# Relay_Shield_v3_0.net
KiCad netlist of a schematic drawn in EAGLE
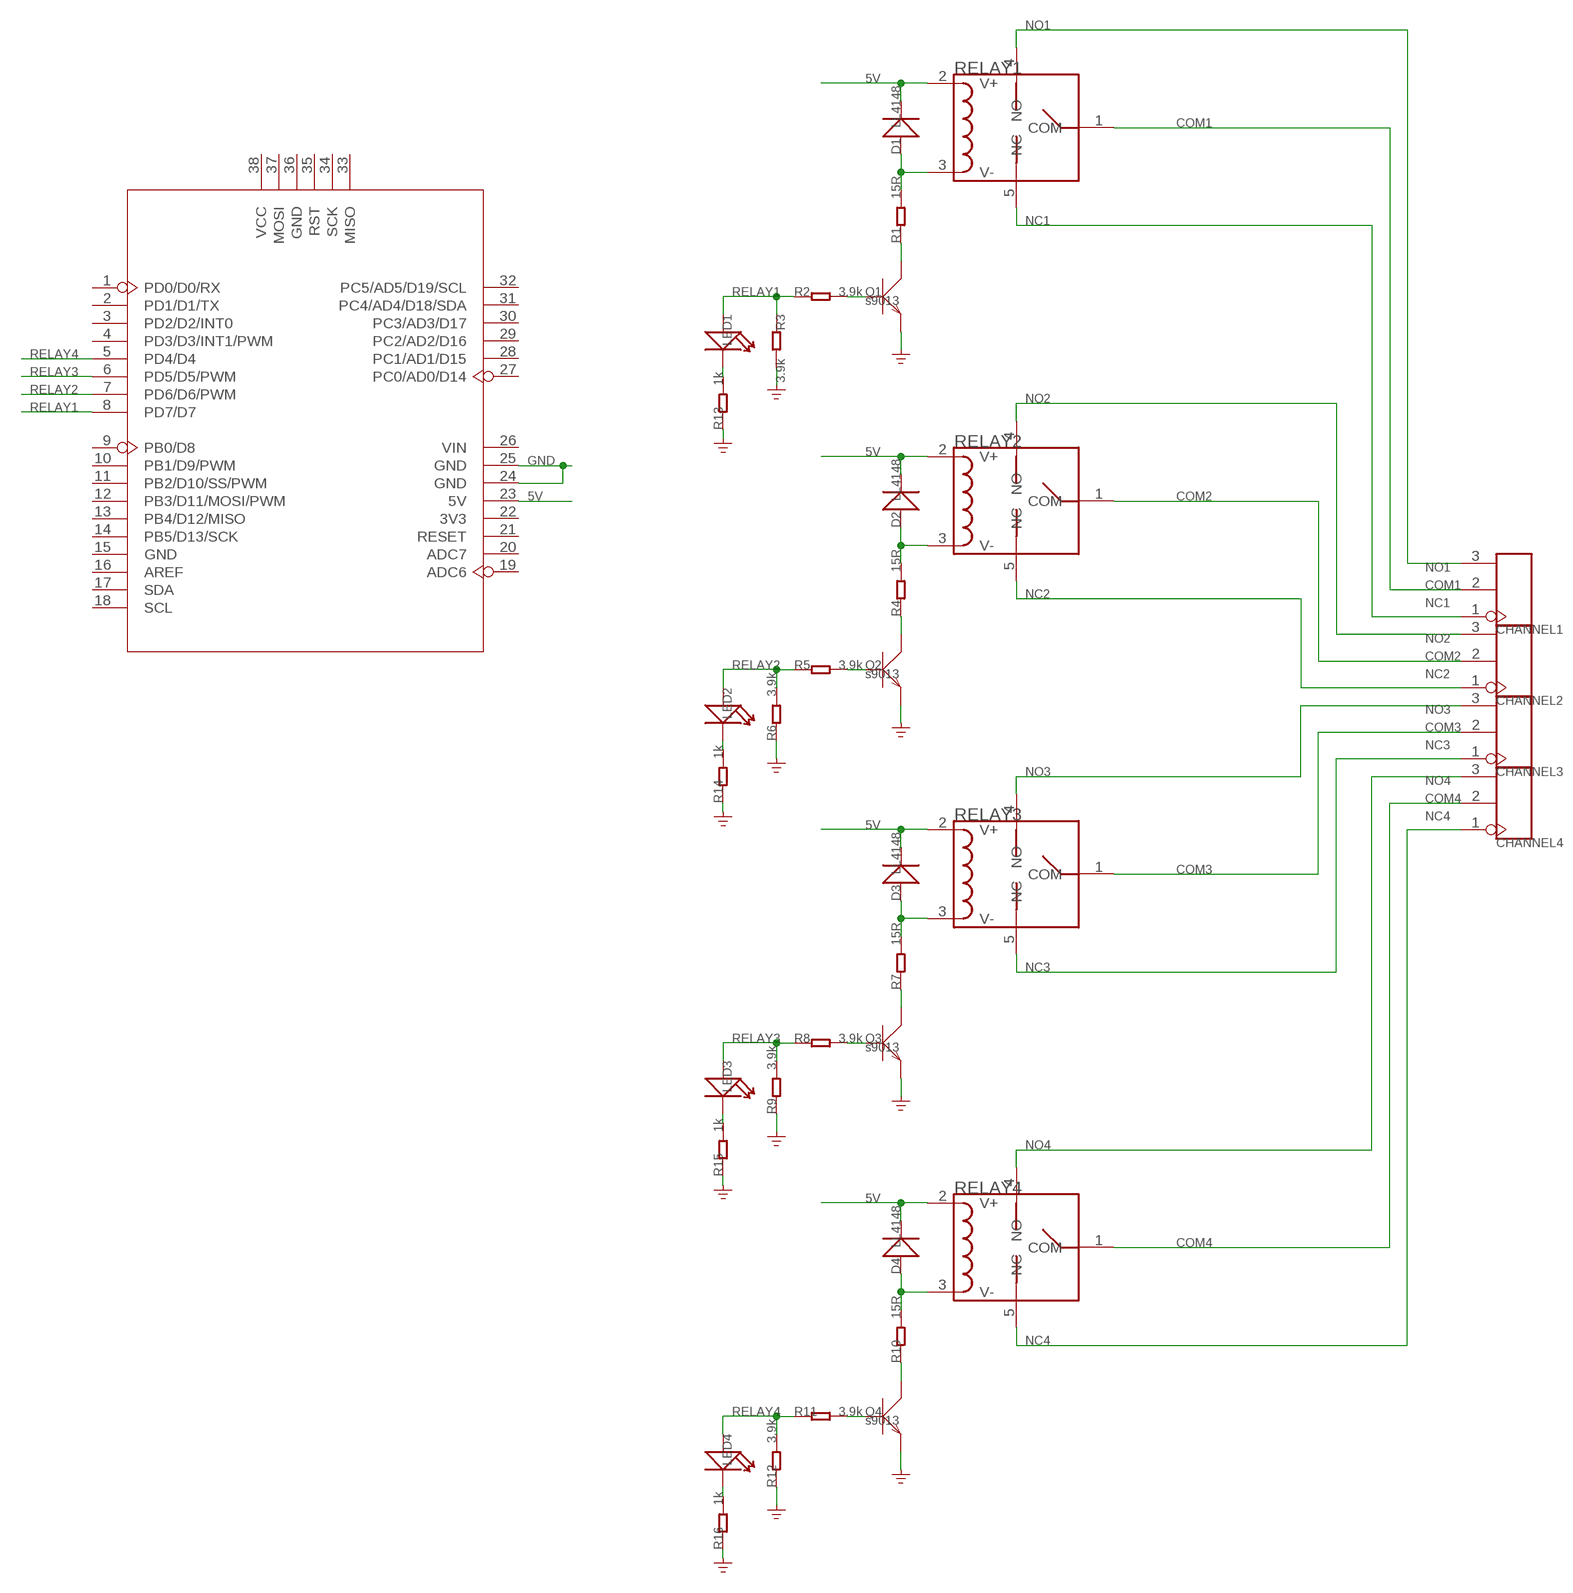
[diagram p0: schematic, sheet 1]
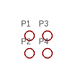
[diagram p1: schematic, sheet 2]

(export (version "E")
  (design (tool "Eeschema 10.0.6"))
  (components
    (comp (ref "P1")
      (value "PAD-MARK")
      (footprint "eagle-import:ROUND-MARK-1.0")
      (fields (field (name "PARTNO") "DNP"))
      (libsource (lib "eagle-import") (part "PAD-MARK"))
    )
    (comp (ref "P2")
      (value "PAD-MARK")
      (footprint "eagle-import:ROUND-MARK-1.0")
      (fields (field (name "PARTNO") "DNP"))
      (libsource (lib "eagle-import") (part "PAD-MARK"))
    )
    (comp (ref "P3")
      (value "PAD-MARK")
      (footprint "eagle-import:ROUND-MARK-1.0")
      (fields (field (name "PARTNO") "DNP"))
      (libsource (lib "eagle-import") (part "PAD-MARK"))
    )
    (comp (ref "P4")
      (value "PAD-MARK")
      (footprint "eagle-import:ROUND-MARK-1.0")
      (fields (field (name "PARTNO") "DNP"))
      (libsource (lib "eagle-import") (part "PAD-MARK"))
    )
    (comp (ref "CHANNEL1")
      (value "SCREW-TERMINAL-3P'3.5'")
      (footprint "eagle-import:3P-3.5")
      (libsource (lib "eagle-import") (part "SCREW-TERMINAL-3P'3.5'"))
    )
    (comp (ref "CHANNEL2")
      (value "SCREW-TERMINAL-3P'3.5'")
      (footprint "eagle-import:3P-3.5")
      (libsource (lib "eagle-import") (part "SCREW-TERMINAL-3P'3.5'"))
    )
    (comp (ref "CHANNEL3")
      (value "SCREW-TERMINAL-3P'3.5'")
      (footprint "eagle-import:3P-3.5")
      (libsource (lib "eagle-import") (part "SCREW-TERMINAL-3P'3.5'"))
    )
    (comp (ref "CHANNEL4")
      (value "SCREW-TERMINAL-3P'3.5'")
      (footprint "eagle-import:3P-3.5")
      (libsource (lib "eagle-import") (part "SCREW-TERMINAL-3P'3.5'"))
    )
    (comp (ref "D1")
      (value "LL4148")
      (footprint "eagle-import:LL-34")
      (libsource (lib "eagle-import") (part "D'1N4148-SMD'"))
    )
    (comp (ref "D2")
      (value "LL4148")
      (footprint "eagle-import:LL-34")
      (libsource (lib "eagle-import") (part "D'1N4148-SMD'"))
    )
    (comp (ref "D3")
      (value "LL4148")
      (footprint "eagle-import:LL-34")
      (libsource (lib "eagle-import") (part "D'1N4148-SMD'"))
    )
    (comp (ref "D4")
      (value "LL4148")
      (footprint "eagle-import:LL-34")
      (libsource (lib "eagle-import") (part "D'1N4148-SMD'"))
    )
    (comp (ref "LED1")
      (value "LED'0603'")
      (footprint "eagle-import:LED-0603")
      (libsource (lib "eagle-import") (part "LED'0603'"))
    )
    (comp (ref "LED2")
      (value "LED'0603'")
      (footprint "eagle-import:LED-0603")
      (libsource (lib "eagle-import") (part "LED'0603'"))
    )
    (comp (ref "LED3")
      (value "LED'0603'")
      (footprint "eagle-import:LED-0603")
      (libsource (lib "eagle-import") (part "LED'0603'"))
    )
    (comp (ref "LED4")
      (value "LED'0603'")
      (footprint "eagle-import:LED-0603")
      (libsource (lib "eagle-import") (part "LED'0603'"))
    )
    (comp (ref "Q1")
      (value "s9013")
      (footprint "eagle-import:SOT23")
      (libsource (lib "eagle-import") (part "TRANSISTOR-NPN-SOT23"))
    )
    (comp (ref "Q2")
      (value "s9013")
      (footprint "eagle-import:SOT23")
      (libsource (lib "eagle-import") (part "TRANSISTOR-NPN-SOT23"))
    )
    (comp (ref "Q3")
      (value "s9013")
      (footprint "eagle-import:SOT23")
      (libsource (lib "eagle-import") (part "TRANSISTOR-NPN-SOT23"))
    )
    (comp (ref "Q4")
      (value "s9013")
      (footprint "eagle-import:SOT23")
      (libsource (lib "eagle-import") (part "TRANSISTOR-NPN-SOT23"))
    )
    (comp (ref "R1")
      (value "15R")
      (footprint "eagle-import:R0603")
      (libsource (lib "eagle-import") (part "R-0603"))
    )
    (comp (ref "R2")
      (value "3.9k")
      (footprint "eagle-import:R0603")
      (libsource (lib "eagle-import") (part "R-0603"))
    )
    (comp (ref "R3")
      (value "3.9k")
      (footprint "eagle-import:R0603")
      (libsource (lib "eagle-import") (part "R-0603"))
    )
    (comp (ref "R4")
      (value "15R")
      (footprint "eagle-import:R0603")
      (libsource (lib "eagle-import") (part "R-0603"))
    )
    (comp (ref "R5")
      (value "3.9k")
      (footprint "eagle-import:R0603")
      (libsource (lib "eagle-import") (part "R-0603"))
    )
    (comp (ref "R6")
      (value "3.9k")
      (footprint "eagle-import:R0603")
      (libsource (lib "eagle-import") (part "R-0603"))
    )
    (comp (ref "R7")
      (value "15R")
      (footprint "eagle-import:R0603")
      (libsource (lib "eagle-import") (part "R-0603"))
    )
    (comp (ref "R8")
      (value "3.9k")
      (footprint "eagle-import:R0603")
      (libsource (lib "eagle-import") (part "R-0603"))
    )
    (comp (ref "R9")
      (value "3.9k")
      (footprint "eagle-import:R0603")
      (libsource (lib "eagle-import") (part "R-0603"))
    )
    (comp (ref "R10")
      (value "15R")
      (footprint "eagle-import:R0603")
      (libsource (lib "eagle-import") (part "R-0603"))
    )
    (comp (ref "R11")
      (value "3.9k")
      (footprint "eagle-import:R0603")
      (libsource (lib "eagle-import") (part "R-0603"))
    )
    (comp (ref "R12")
      (value "3.9k")
      (footprint "eagle-import:R0603")
      (libsource (lib "eagle-import") (part "R-0603"))
    )
    (comp (ref "R13")
      (value "1k")
      (footprint "eagle-import:R0603")
      (libsource (lib "eagle-import") (part "R-0603"))
    )
    (comp (ref "R14")
      (value "1k")
      (footprint "eagle-import:R0603")
      (libsource (lib "eagle-import") (part "R-0603"))
    )
    (comp (ref "R15")
      (value "1k")
      (footprint "eagle-import:R0603")
      (libsource (lib "eagle-import") (part "R-0603"))
    )
    (comp (ref "R16")
      (value "1k")
      (footprint "eagle-import:R0603")
      (libsource (lib "eagle-import") (part "R-0603"))
    )
    (comp (ref "RELAY1")
      (value "RELAY-HLS8L-DC5V-S-C")
      (footprint "eagle-import:5P-19.0X15.5X15.8H")
      (libsource (lib "eagle-import") (part "RELAY-HLS8L-DC5V-S-C"))
    )
    (comp (ref "RELAY2")
      (value "RELAY-HLS8L-DC5V-S-C")
      (footprint "eagle-import:5P-19.0X15.5X15.8H")
      (libsource (lib "eagle-import") (part "RELAY-HLS8L-DC5V-S-C"))
    )
    (comp (ref "RELAY3")
      (value "RELAY-HLS8L-DC5V-S-C")
      (footprint "eagle-import:5P-19.0X15.5X15.8H")
      (libsource (lib "eagle-import") (part "RELAY-HLS8L-DC5V-S-C"))
    )
    (comp (ref "RELAY4")
      (value "RELAY-HLS8L-DC5V-S-C")
      (footprint "eagle-import:5P-19.0X15.5X15.8H")
      (libsource (lib "eagle-import") (part "RELAY-HLS8L-DC5V-S-C"))
    )
    (comp (ref "U2")
      (value "ARDUINO-38P")
      (footprint "eagle-import:ARDUINO-38P-WITH_-SILK-500519002")
      (libsource (lib "eagle-import") (part "ARDUINO-38P"))
    )
  )
  (nets
    (net (code "1") (name "5V") (class "Default")
      (node (ref "D1") (pin "C") (pinfunction "-_C") (pintype "passive"))
      (node (ref "D2") (pin "C") (pinfunction "-_C") (pintype "passive"))
      (node (ref "D3") (pin "C") (pinfunction "-_C") (pintype "passive"))
      (node (ref "D4") (pin "C") (pinfunction "-_C") (pintype "passive"))
      (node (ref "RELAY1") (pin "2") (pinfunction "V+_2") (pintype "bidirectional"))
      (node (ref "RELAY2") (pin "2") (pinfunction "V+_2") (pintype "bidirectional"))
      (node (ref "RELAY3") (pin "2") (pinfunction "V+_2") (pintype "bidirectional"))
      (node (ref "RELAY4") (pin "2") (pinfunction "V+_2") (pintype "bidirectional"))
      (node (ref "U2") (pin "23") (pinfunction "5V_23") (pintype "bidirectional"))
    )
    (net (code "2") (name "COM1") (class "Default")
      (node (ref "CHANNEL1") (pin "2") (pinfunction "P$2_2") (pintype "bidirectional"))
      (node (ref "RELAY1") (pin "1") (pinfunction "COM_1") (pintype "bidirectional"))
    )
    (net (code "3") (name "COM2") (class "Default")
      (node (ref "CHANNEL2") (pin "2") (pinfunction "P$2_2") (pintype "bidirectional"))
      (node (ref "RELAY2") (pin "1") (pinfunction "COM_1") (pintype "bidirectional"))
    )
    (net (code "4") (name "COM3") (class "Default")
      (node (ref "CHANNEL3") (pin "2") (pinfunction "P$2_2") (pintype "bidirectional"))
      (node (ref "RELAY3") (pin "1") (pinfunction "COM_1") (pintype "bidirectional"))
    )
    (net (code "5") (name "COM4") (class "Default")
      (node (ref "CHANNEL4") (pin "2") (pinfunction "P$2_2") (pintype "bidirectional"))
      (node (ref "RELAY4") (pin "1") (pinfunction "COM_1") (pintype "bidirectional"))
    )
    (net (code "6") (name "GND") (class "Default")
      (node (ref "Q1") (pin "2") (pinfunction "E_2") (pintype "passive"))
      (node (ref "Q2") (pin "2") (pinfunction "E_2") (pintype "passive"))
      (node (ref "Q3") (pin "2") (pinfunction "E_2") (pintype "passive"))
      (node (ref "Q4") (pin "2") (pinfunction "E_2") (pintype "passive"))
      (node (ref "R12") (pin "1") (pinfunction "1_1") (pintype "passive"))
      (node (ref "R13") (pin "1") (pinfunction "1_1") (pintype "passive"))
      (node (ref "R14") (pin "1") (pinfunction "1_1") (pintype "passive"))
      (node (ref "R15") (pin "1") (pinfunction "1_1") (pintype "passive"))
      (node (ref "R16") (pin "1") (pinfunction "1_1") (pintype "passive"))
      (node (ref "R3") (pin "2") (pinfunction "2_2") (pintype "passive"))
      (node (ref "R6") (pin "1") (pinfunction "1_1") (pintype "passive"))
      (node (ref "R9") (pin "1") (pinfunction "1_1") (pintype "passive"))
      (node (ref "U2") (pin "24") (pinfunction "GND_24") (pintype "bidirectional"))
      (node (ref "U2") (pin "25") (pinfunction "GND_25") (pintype "bidirectional"))
    )
    (net (code "7") (name "NC1") (class "Default")
      (node (ref "CHANNEL1") (pin "1") (pinfunction "P$1_1") (pintype "bidirectional"))
      (node (ref "RELAY1") (pin "5") (pinfunction "NC_5") (pintype "bidirectional"))
    )
    (net (code "8") (name "NC2") (class "Default")
      (node (ref "CHANNEL2") (pin "1") (pinfunction "P$1_1") (pintype "bidirectional"))
      (node (ref "RELAY2") (pin "5") (pinfunction "NC_5") (pintype "bidirectional"))
    )
    (net (code "9") (name "NC3") (class "Default")
      (node (ref "CHANNEL3") (pin "1") (pinfunction "P$1_1") (pintype "bidirectional"))
      (node (ref "RELAY3") (pin "5") (pinfunction "NC_5") (pintype "bidirectional"))
    )
    (net (code "10") (name "NC4") (class "Default")
      (node (ref "CHANNEL4") (pin "1") (pinfunction "P$1_1") (pintype "bidirectional"))
      (node (ref "RELAY4") (pin "5") (pinfunction "NC_5") (pintype "bidirectional"))
    )
    (net (code "11") (name "NO1") (class "Default")
      (node (ref "CHANNEL1") (pin "3") (pinfunction "P$3_3") (pintype "bidirectional"))
      (node (ref "RELAY1") (pin "4") (pinfunction "NO_4") (pintype "bidirectional"))
    )
    (net (code "12") (name "NO2") (class "Default")
      (node (ref "CHANNEL2") (pin "3") (pinfunction "P$3_3") (pintype "bidirectional"))
      (node (ref "RELAY2") (pin "4") (pinfunction "NO_4") (pintype "bidirectional"))
    )
    (net (code "13") (name "NO3") (class "Default")
      (node (ref "CHANNEL3") (pin "3") (pinfunction "P$3_3") (pintype "bidirectional"))
      (node (ref "RELAY3") (pin "4") (pinfunction "NO_4") (pintype "bidirectional"))
    )
    (net (code "14") (name "NO4") (class "Default")
      (node (ref "CHANNEL4") (pin "3") (pinfunction "P$3_3") (pintype "bidirectional"))
      (node (ref "RELAY4") (pin "4") (pinfunction "NO_4") (pintype "bidirectional"))
    )
    (net (code "15") (name "Net-(D1-+)") (class "Default")
      (node (ref "D1") (pin "A") (pinfunction "+_A") (pintype "passive"))
      (node (ref "R1") (pin "2") (pinfunction "2_2") (pintype "passive"))
      (node (ref "RELAY1") (pin "3") (pinfunction "V-_3") (pintype "bidirectional"))
    )
    (net (code "16") (name "Net-(D2-+)") (class "Default")
      (node (ref "D2") (pin "A") (pinfunction "+_A") (pintype "passive"))
      (node (ref "R4") (pin "2") (pinfunction "2_2") (pintype "passive"))
      (node (ref "RELAY2") (pin "3") (pinfunction "V-_3") (pintype "bidirectional"))
    )
    (net (code "17") (name "Net-(D3-+)") (class "Default")
      (node (ref "D3") (pin "A") (pinfunction "+_A") (pintype "passive"))
      (node (ref "R7") (pin "2") (pinfunction "2_2") (pintype "passive"))
      (node (ref "RELAY3") (pin "3") (pinfunction "V-_3") (pintype "bidirectional"))
    )
    (net (code "18") (name "Net-(D4-+)") (class "Default")
      (node (ref "D4") (pin "A") (pinfunction "+_A") (pintype "passive"))
      (node (ref "R10") (pin "2") (pinfunction "2_2") (pintype "passive"))
      (node (ref "RELAY4") (pin "3") (pinfunction "V-_3") (pintype "bidirectional"))
    )
    (net (code "19") (name "Net-(LED1-Pad-)") (class "Default")
      (node (ref "LED1") (pin "-") (pinfunction "-_-") (pintype "passive"))
      (node (ref "R13") (pin "2") (pinfunction "2_2") (pintype "passive"))
    )
    (net (code "20") (name "Net-(LED2-Pad-)") (class "Default")
      (node (ref "LED2") (pin "-") (pinfunction "-_-") (pintype "passive"))
      (node (ref "R14") (pin "2") (pinfunction "2_2") (pintype "passive"))
    )
    (net (code "21") (name "Net-(LED3-Pad-)") (class "Default")
      (node (ref "LED3") (pin "-") (pinfunction "-_-") (pintype "passive"))
      (node (ref "R15") (pin "2") (pinfunction "2_2") (pintype "passive"))
    )
    (net (code "22") (name "Net-(LED4-Pad-)") (class "Default")
      (node (ref "LED4") (pin "-") (pinfunction "-_-") (pintype "passive"))
      (node (ref "R16") (pin "2") (pinfunction "2_2") (pintype "passive"))
    )
    (net (code "23") (name "Net-(Q1-B)") (class "Default")
      (node (ref "Q1") (pin "1") (pinfunction "B_1") (pintype "passive"))
      (node (ref "R2") (pin "2") (pinfunction "2_2") (pintype "passive"))
    )
    (net (code "24") (name "Net-(Q1-C)") (class "Default")
      (node (ref "Q1") (pin "3") (pinfunction "C_3") (pintype "passive"))
      (node (ref "R1") (pin "1") (pinfunction "1_1") (pintype "passive"))
    )
    (net (code "25") (name "Net-(Q2-B)") (class "Default")
      (node (ref "Q2") (pin "1") (pinfunction "B_1") (pintype "passive"))
      (node (ref "R5") (pin "2") (pinfunction "2_2") (pintype "passive"))
    )
    (net (code "26") (name "Net-(Q2-C)") (class "Default")
      (node (ref "Q2") (pin "3") (pinfunction "C_3") (pintype "passive"))
      (node (ref "R4") (pin "1") (pinfunction "1_1") (pintype "passive"))
    )
    (net (code "27") (name "Net-(Q3-B)") (class "Default")
      (node (ref "Q3") (pin "1") (pinfunction "B_1") (pintype "passive"))
      (node (ref "R8") (pin "2") (pinfunction "2_2") (pintype "passive"))
    )
    (net (code "28") (name "Net-(Q3-C)") (class "Default")
      (node (ref "Q3") (pin "3") (pinfunction "C_3") (pintype "passive"))
      (node (ref "R7") (pin "1") (pinfunction "1_1") (pintype "passive"))
    )
    (net (code "29") (name "Net-(Q4-B)") (class "Default")
      (node (ref "Q4") (pin "1") (pinfunction "B_1") (pintype "passive"))
      (node (ref "R11") (pin "2") (pinfunction "2_2") (pintype "passive"))
    )
    (net (code "30") (name "Net-(Q4-C)") (class "Default")
      (node (ref "Q4") (pin "3") (pinfunction "C_3") (pintype "passive"))
      (node (ref "R10") (pin "1") (pinfunction "1_1") (pintype "passive"))
    )
    (net (code "31") (name "RELAY1") (class "Default")
      (node (ref "LED1") (pin "+") (pinfunction "+_+") (pintype "passive"))
      (node (ref "R2") (pin "1") (pinfunction "1_1") (pintype "passive"))
      (node (ref "R3") (pin "1") (pinfunction "1_1") (pintype "passive"))
      (node (ref "U2") (pin "8") (pinfunction "PD7/D7_8") (pintype "bidirectional"))
    )
    (net (code "32") (name "RELAY2") (class "Default")
      (node (ref "LED2") (pin "+") (pinfunction "+_+") (pintype "passive"))
      (node (ref "R5") (pin "1") (pinfunction "1_1") (pintype "passive"))
      (node (ref "R6") (pin "2") (pinfunction "2_2") (pintype "passive"))
      (node (ref "U2") (pin "7") (pinfunction "PD6/D6/PWM_7") (pintype "bidirectional"))
    )
    (net (code "33") (name "RELAY3") (class "Default")
      (node (ref "LED3") (pin "+") (pinfunction "+_+") (pintype "passive"))
      (node (ref "R8") (pin "1") (pinfunction "1_1") (pintype "passive"))
      (node (ref "R9") (pin "2") (pinfunction "2_2") (pintype "passive"))
      (node (ref "U2") (pin "6") (pinfunction "PD5/D5/PWM_6") (pintype "bidirectional"))
    )
    (net (code "34") (name "RELAY4") (class "Default")
      (node (ref "LED4") (pin "+") (pinfunction "+_+") (pintype "passive"))
      (node (ref "R11") (pin "1") (pinfunction "1_1") (pintype "passive"))
      (node (ref "R12") (pin "2") (pinfunction "2_2") (pintype "passive"))
      (node (ref "U2") (pin "5") (pinfunction "PD4/D4_5") (pintype "bidirectional"))
    )
    (net (code "35") (name "unconnected-(U2-3V3-Pad22)") (class "Default")
      (node (ref "U2") (pin "22") (pinfunction "3V3_22") (pintype "bidirectional"))
    )
    (net (code "36") (name "unconnected-(U2-ADC6-Pad19)") (class "Default")
      (node (ref "U2") (pin "19") (pinfunction "ADC6_19") (pintype "bidirectional"))
    )
    (net (code "37") (name "unconnected-(U2-ADC7-Pad20)") (class "Default")
      (node (ref "U2") (pin "20") (pinfunction "ADC7_20") (pintype "bidirectional"))
    )
    (net (code "38") (name "unconnected-(U2-AREF-Pad16)") (class "Default")
      (node (ref "U2") (pin "16") (pinfunction "AREF_16") (pintype "bidirectional"))
    )
    (net (code "39") (name "unconnected-(U2-GND-Pad15)") (class "Default")
      (node (ref "U2") (pin "15") (pinfunction "GND_15") (pintype "bidirectional"))
    )
    (net (code "40") (name "unconnected-(U2-GND-Pad36)") (class "Default")
      (node (ref "U2") (pin "36") (pinfunction "GND_36") (pintype "bidirectional"))
    )
    (net (code "41") (name "unconnected-(U2-MISO-Pad33)") (class "Default")
      (node (ref "U2") (pin "33") (pinfunction "MISO_33") (pintype "bidirectional"))
    )
    (net (code "42") (name "unconnected-(U2-MOSI-Pad37)") (class "Default")
      (node (ref "U2") (pin "37") (pinfunction "MOSI_37") (pintype "bidirectional"))
    )
    (net (code "43") (name "unconnected-(U2-PB0{slash}D8-Pad9)") (class "Default")
      (node (ref "U2") (pin "9") (pinfunction "PB0/D8_9") (pintype "bidirectional"))
    )
    (net (code "44") (name "unconnected-(U2-PB1{slash}D9{slash}PWM-Pad10)") (class "Default")
      (node (ref "U2") (pin "10") (pinfunction "PB1/D9/PWM_10") (pintype "bidirectional"))
    )
    (net (code "45") (name "unconnected-(U2-PB2{slash}D10{slash}SS{slash}PWM-Pad11)") (class "Default")
      (node (ref "U2") (pin "11") (pinfunction "PB2/D10/SS/PWM_11") (pintype "bidirectional"))
    )
    (net (code "46") (name "unconnected-(U2-PB3{slash}D11{slash}MOSI{slash}PWM-Pad12)") (class "Default")
      (node (ref "U2") (pin "12") (pinfunction "PB3/D11/MOSI/PWM_12") (pintype "bidirectional"))
    )
    (net (code "47") (name "unconnected-(U2-PB4{slash}D12{slash}MISO-Pad13)") (class "Default")
      (node (ref "U2") (pin "13") (pinfunction "PB4/D12/MISO_13") (pintype "bidirectional"))
    )
    (net (code "48") (name "unconnected-(U2-PB5{slash}D13{slash}SCK-Pad14)") (class "Default")
      (node (ref "U2") (pin "14") (pinfunction "PB5/D13/SCK_14") (pintype "bidirectional"))
    )
    (net (code "49") (name "unconnected-(U2-PC0{slash}AD0{slash}D14-Pad27)") (class "Default")
      (node (ref "U2") (pin "27") (pinfunction "PC0/AD0/D14_27") (pintype "bidirectional"))
    )
    (net (code "50") (name "unconnected-(U2-PC1{slash}AD1{slash}D15-Pad28)") (class "Default")
      (node (ref "U2") (pin "28") (pinfunction "PC1/AD1/D15_28") (pintype "bidirectional"))
    )
    (net (code "51") (name "unconnected-(U2-PC2{slash}AD2{slash}D16-Pad29)") (class "Default")
      (node (ref "U2") (pin "29") (pinfunction "PC2/AD2/D16_29") (pintype "bidirectional"))
    )
    (net (code "52") (name "unconnected-(U2-PC3{slash}AD3{slash}D17-Pad30)") (class "Default")
      (node (ref "U2") (pin "30") (pinfunction "PC3/AD3/D17_30") (pintype "bidirectional"))
    )
    (net (code "53") (name "unconnected-(U2-PC4{slash}AD4{slash}D18{slash}SDA-Pad31)") (class "Default")
      (node (ref "U2") (pin "31") (pinfunction "PC4/AD4/D18/SDA_31") (pintype "bidirectional"))
    )
    (net (code "54") (name "unconnected-(U2-PC5{slash}AD5{slash}D19{slash}SCL-Pad32)") (class "Default")
      (node (ref "U2") (pin "32") (pinfunction "PC5/AD5/D19/SCL_32") (pintype "bidirectional"))
    )
    (net (code "55") (name "unconnected-(U2-PD0{slash}D0{slash}RX-Pad1)") (class "Default")
      (node (ref "U2") (pin "1") (pinfunction "PD0/D0/RX_1") (pintype "bidirectional"))
    )
    (net (code "56") (name "unconnected-(U2-PD1{slash}D1{slash}TX-Pad2)") (class "Default")
      (node (ref "U2") (pin "2") (pinfunction "PD1/D1/TX_2") (pintype "bidirectional"))
    )
    (net (code "57") (name "unconnected-(U2-PD2{slash}D2{slash}INT0-Pad3)") (class "Default")
      (node (ref "U2") (pin "3") (pinfunction "PD2/D2/INT0_3") (pintype "bidirectional"))
    )
    (net (code "58") (name "unconnected-(U2-PD3{slash}D3{slash}INT1{slash}PWM-Pad4)") (class "Default")
      (node (ref "U2") (pin "4") (pinfunction "PD3/D3/INT1/PWM_4") (pintype "bidirectional"))
    )
    (net (code "59") (name "unconnected-(U2-RESET-Pad21)") (class "Default")
      (node (ref "U2") (pin "21") (pinfunction "RESET_21") (pintype "bidirectional"))
    )
    (net (code "60") (name "unconnected-(U2-RST-Pad35)") (class "Default")
      (node (ref "U2") (pin "35") (pinfunction "RST_35") (pintype "bidirectional"))
    )
    (net (code "61") (name "unconnected-(U2-SCK-Pad34)") (class "Default")
      (node (ref "U2") (pin "34") (pinfunction "SCK_34") (pintype "bidirectional"))
    )
    (net (code "62") (name "unconnected-(U2-SCL-Pad18)") (class "Default")
      (node (ref "U2") (pin "18") (pinfunction "SCL_18") (pintype "bidirectional"))
    )
    (net (code "63") (name "unconnected-(U2-SDA-Pad17)") (class "Default")
      (node (ref "U2") (pin "17") (pinfunction "SDA_17") (pintype "bidirectional"))
    )
    (net (code "64") (name "unconnected-(U2-VCC-Pad38)") (class "Default")
      (node (ref "U2") (pin "38") (pinfunction "VCC_38") (pintype "bidirectional"))
    )
    (net (code "65") (name "unconnected-(U2-VIN-Pad26)") (class "Default")
      (node (ref "U2") (pin "26") (pinfunction "VIN_26") (pintype "bidirectional"))
    )
  )
)
